# Micro-OLED_I2C.net
KiCad netlist of a schematic drawn in EAGLE
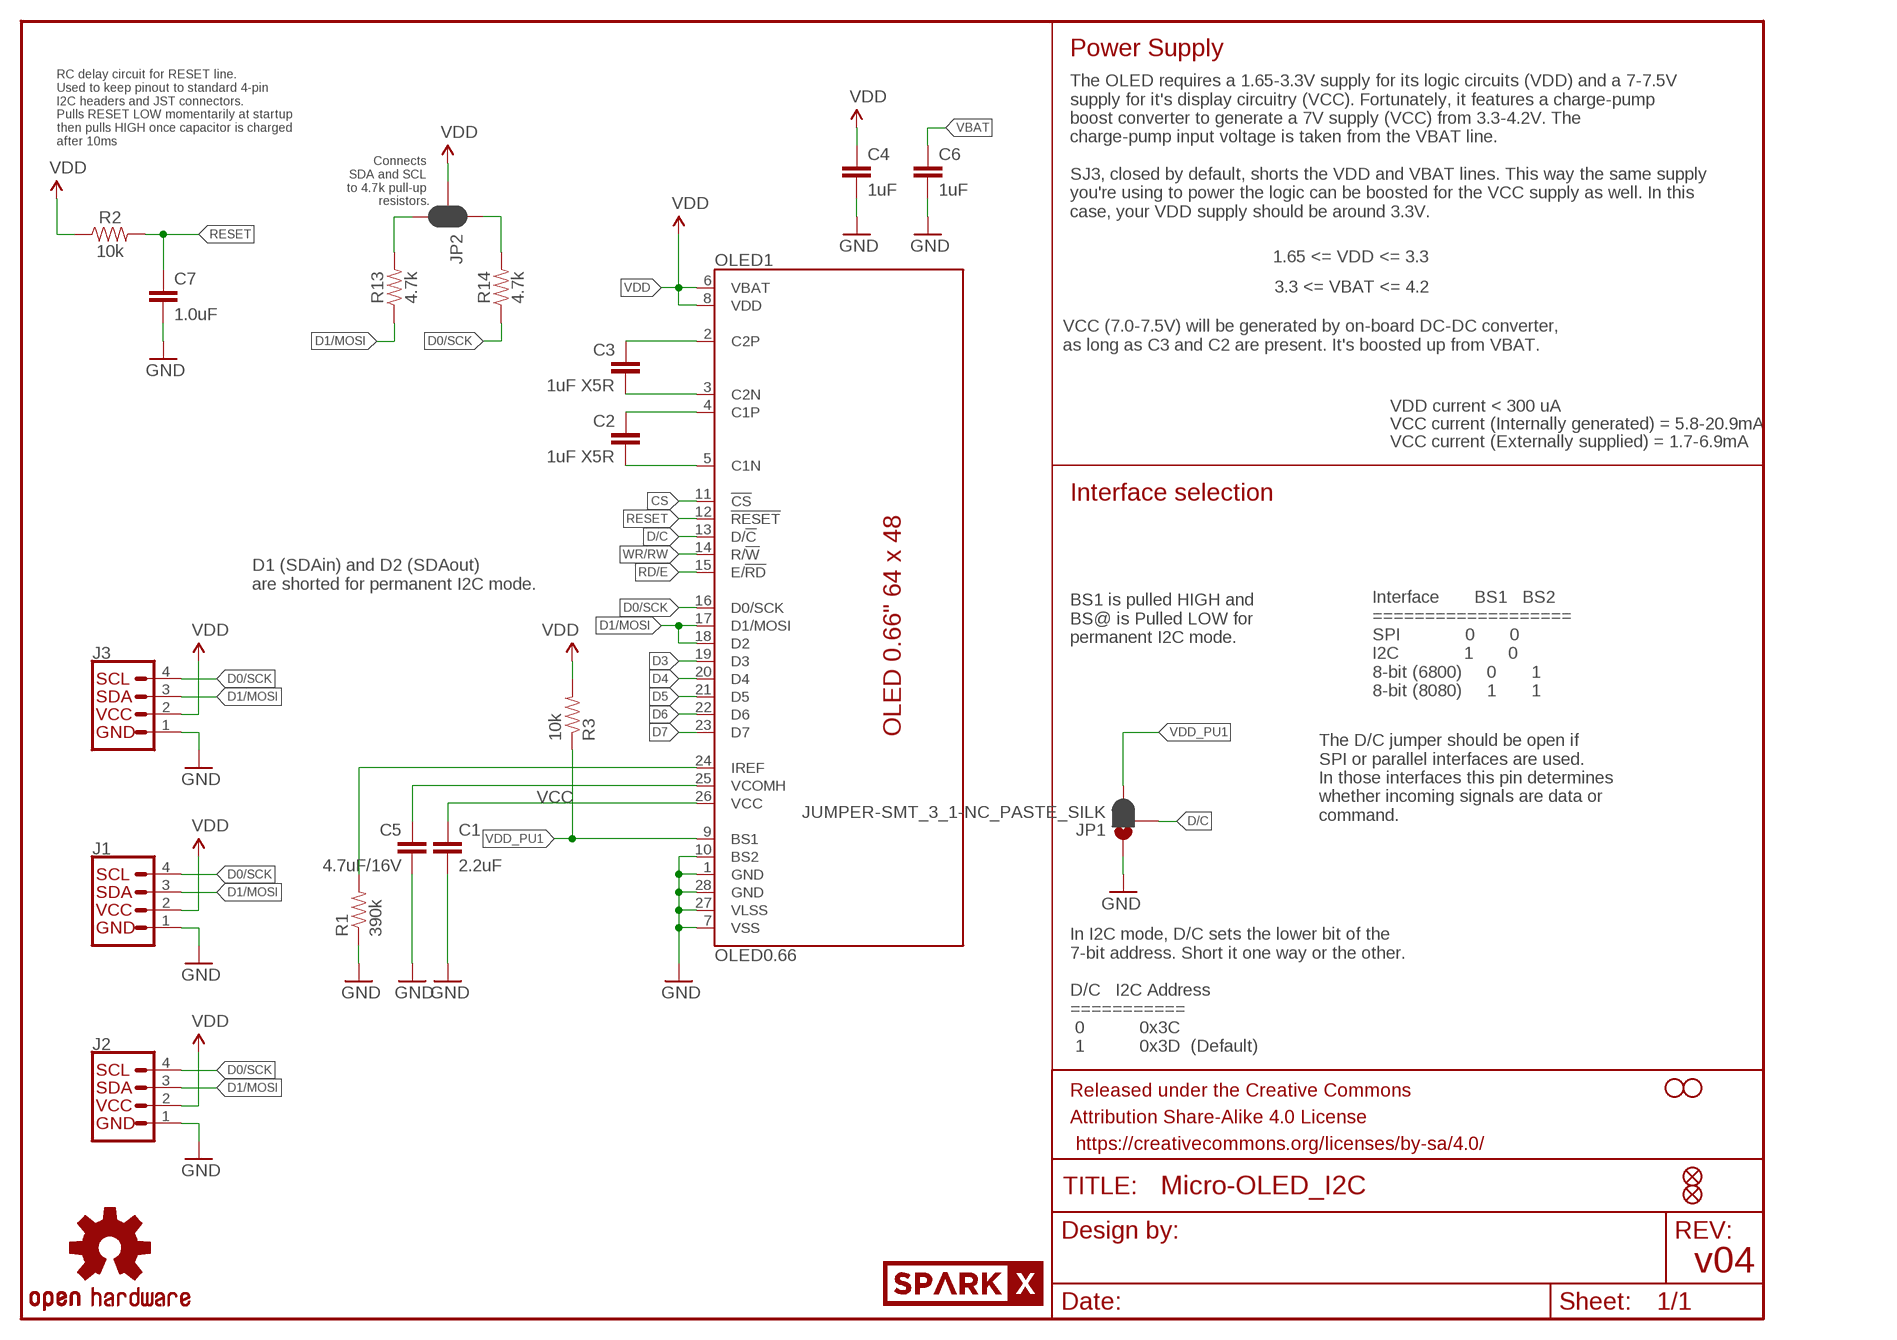
[diagram p0: schematic, sheet 1]

(export (version "E")
  (design (tool "Eeschema 10.0.6"))
  (components
    (comp (ref "C1")
      (value "2.2uF")
      (footprint "eagle-import:0805")
      (libsource (lib "eagle-import") (part "CAP0805"))
    )
    (comp (ref "C2")
      (value "1uF X5R")
      (footprint "eagle-import:0805")
      (libsource (lib "eagle-import") (part "CAP0805"))
    )
    (comp (ref "C3")
      (value "1uF X5R")
      (footprint "eagle-import:0805")
      (libsource (lib "eagle-import") (part "CAP0805"))
    )
    (comp (ref "C4")
      (value "1uF")
      (footprint "eagle-import:0603-CAP")
      (libsource (lib "eagle-import") (part "CAP0603-CAP"))
    )
    (comp (ref "C5")
      (value "4.7uF/16V")
      (footprint "eagle-import:1206")
      (libsource (lib "eagle-import") (part "CAP1206"))
    )
    (comp (ref "C6")
      (value "1uF")
      (footprint "eagle-import:0603-CAP")
      (libsource (lib "eagle-import") (part "CAP0603-CAP"))
    )
    (comp (ref "C7")
      (value "1.0uF")
      (footprint "eagle-import:0603")
      (libsource (lib "eagle-import") (part "1.0UF-0603-16V-10%"))
    )
    (comp (ref "FID1")
      (value "FIDUCIAL1X2")
      (footprint "eagle-import:FIDUCIAL-1X2")
      (libsource (lib "eagle-import") (part "FIDUCIAL1X2"))
    )
    (comp (ref "FID2")
      (value "FIDUCIAL1X2")
      (footprint "eagle-import:FIDUCIAL-1X2")
      (libsource (lib "eagle-import") (part "FIDUCIAL1X2"))
    )
    (comp (ref "FRAME1")
      (value "FRAME-LETTER")
      (footprint "eagle-import:CREATIVE_COMMONS")
      (libsource (lib "eagle-import") (part "FRAME-LETTER"))
    )
    (comp (ref "H1")
      (value "STAND-OFF")
      (footprint "eagle-import:STAND-OFF")
      (libsource (lib "eagle-import") (part "STAND-OFF"))
    )
    (comp (ref "H2")
      (value "STAND-OFF")
      (footprint "eagle-import:STAND-OFF")
      (libsource (lib "eagle-import") (part "STAND-OFF"))
    )
    (comp (ref "J1")
      (value "I2C_STANDARDJS-1MM")
      (footprint "eagle-import:1X04_1MM_RA")
      (libsource (lib "eagle-import") (part "I2C_STANDARDJS-1MM"))
    )
    (comp (ref "J2")
      (value "I2C_STANDARDJS-1MM")
      (footprint "eagle-import:1X04_1MM_RA")
      (libsource (lib "eagle-import") (part "I2C_STANDARDJS-1MM"))
    )
    (comp (ref "J3")
      (value "I2C_STANDARD_NO_SILK")
      (footprint "eagle-import:1X04_NO_SILK")
      (libsource (lib "eagle-import") (part "I2C_STANDARD_NO_SILK"))
    )
    (comp (ref "JP1")
      (value "JUMPER-SMT_3_1-NC_PASTE_SILK")
      (footprint "eagle-import:SMT-JUMPER_3_1-NC_PASTE_SILK")
      (libsource (lib "eagle-import") (part "JUMPER-SMT_3_1-NC_PASTE_SILK"))
    )
    (comp (ref "JP2")
      (value "JUMPER-SMT_3_2-NC_PASTE_SILK")
      (footprint "eagle-import:SMT-JUMPER_3_2-NC_PASTE_SILK")
      (libsource (lib "eagle-import") (part "JUMPER-SMT_3_2-NC_PASTE_SILK"))
    )
    (comp (ref "LOGO3")
      (value "OSHW-LOGOS")
      (footprint "eagle-import:OSHW-LOGO-S")
      (libsource (lib "eagle-import") (part "OSHW-LOGOS"))
    )
    (comp (ref "OLED1")
      (value "OLED0.66")
      (footprint "eagle-import:OLED-0.66-64X48")
      (libsource (lib "eagle-import") (part "OLED0.66"))
    )
    (comp (ref "R1")
      (value "390k")
      (footprint "eagle-import:0603-RES")
      (libsource (lib "eagle-import") (part "RESISTOR0603-RES"))
    )
    (comp (ref "R2")
      (value "10k")
      (footprint "eagle-import:0603")
      (libsource (lib "eagle-import") (part "10KOHM-0603-1/10W-1%"))
    )
    (comp (ref "R3")
      (value "10k")
      (footprint "eagle-import:0603-RES")
      (libsource (lib "eagle-import") (part "RESISTOR0603-RES"))
    )
    (comp (ref "R13")
      (value "4.7k")
      (footprint "eagle-import:0603")
      (libsource (lib "eagle-import") (part "4.7KOHM-0603-1/10W-1%"))
    )
    (comp (ref "R14")
      (value "4.7k")
      (footprint "eagle-import:0603")
      (libsource (lib "eagle-import") (part "4.7KOHM-0603-1/10W-1%"))
    )
    (comp (ref "U$1")
      (value "SPARKX-LOGO4")
      (footprint "eagle-import:SPARKX-MEDIUM")
      (libsource (lib "eagle-import") (part "SPARKX-LOGO4"))
    )
  )
  (nets
    (net (code "1") (name "/VCC") (class "Default")
      (node (ref "C1") (pin "1") (pinfunction "1_1") (pintype "passive"))
      (node (ref "OLED1") (pin "26") (pinfunction "VCC_26") (pintype "bidirectional"))
    )
    (net (code "2") (name "CS") (class "Default")
      (node (ref "OLED1") (pin "11") (pinfunction "~{CS}_11") (pintype "bidirectional"))
    )
    (net (code "3") (name "D0{slash}SCK") (class "Default")
      (node (ref "J1") (pin "4") (pinfunction "SCL_4") (pintype "passive"))
      (node (ref "J2") (pin "4") (pinfunction "SCL_4") (pintype "passive"))
      (node (ref "J3") (pin "4") (pinfunction "SCL_4") (pintype "passive"))
      (node (ref "OLED1") (pin "16") (pinfunction "D0/SCK_16") (pintype "bidirectional"))
      (node (ref "R14") (pin "1") (pinfunction "1_1") (pintype "passive"))
    )
    (net (code "4") (name "D1{slash}MOSI") (class "Default")
      (node (ref "J1") (pin "3") (pinfunction "SDA_3") (pintype "passive"))
      (node (ref "J2") (pin "3") (pinfunction "SDA_3") (pintype "passive"))
      (node (ref "J3") (pin "3") (pinfunction "SDA_3") (pintype "passive"))
      (node (ref "OLED1") (pin "17") (pinfunction "D1/MOSI_17") (pintype "bidirectional"))
      (node (ref "OLED1") (pin "18") (pinfunction "D2_18") (pintype "bidirectional"))
      (node (ref "R13") (pin "1") (pinfunction "1_1") (pintype "passive"))
    )
    (net (code "5") (name "D3") (class "Default")
      (node (ref "OLED1") (pin "19") (pinfunction "D3_19") (pintype "bidirectional"))
    )
    (net (code "6") (name "D4") (class "Default")
      (node (ref "OLED1") (pin "20") (pinfunction "D4_20") (pintype "bidirectional"))
    )
    (net (code "7") (name "D5") (class "Default")
      (node (ref "OLED1") (pin "21") (pinfunction "D5_21") (pintype "bidirectional"))
    )
    (net (code "8") (name "D6") (class "Default")
      (node (ref "OLED1") (pin "22") (pinfunction "D6_22") (pintype "bidirectional"))
    )
    (net (code "9") (name "D7") (class "Default")
      (node (ref "OLED1") (pin "23") (pinfunction "D7_23") (pintype "bidirectional"))
    )
    (net (code "10") (name "D{slash}C") (class "Default")
      (node (ref "JP1") (pin "2") (pinfunction "2_2") (pintype "passive"))
      (node (ref "OLED1") (pin "13") (pinfunction "D/~{C}_13") (pintype "bidirectional"))
    )
    (net (code "11") (name "GND") (class "Default")
      (node (ref "C1") (pin "2") (pinfunction "2_2") (pintype "passive"))
      (node (ref "C4") (pin "2") (pinfunction "2_2") (pintype "passive"))
      (node (ref "C5") (pin "2") (pinfunction "2_2") (pintype "passive"))
      (node (ref "C6") (pin "2") (pinfunction "2_2") (pintype "passive"))
      (node (ref "C7") (pin "2") (pinfunction "2_2") (pintype "passive"))
      (node (ref "J1") (pin "1") (pinfunction "GND_1") (pintype "power_in"))
      (node (ref "J2") (pin "1") (pinfunction "GND_1") (pintype "power_in"))
      (node (ref "J3") (pin "1") (pinfunction "GND_1") (pintype "power_in"))
      (node (ref "JP1") (pin "1") (pinfunction "1_1") (pintype "passive"))
      (node (ref "OLED1") (pin "1") (pinfunction "GND_1") (pintype "bidirectional"))
      (node (ref "OLED1") (pin "10") (pinfunction "BS2_10") (pintype "bidirectional"))
      (node (ref "OLED1") (pin "27") (pinfunction "VLSS_27") (pintype "bidirectional"))
      (node (ref "OLED1") (pin "28") (pinfunction "GND_28") (pintype "bidirectional"))
      (node (ref "OLED1") (pin "7") (pinfunction "VSS_7") (pintype "bidirectional"))
      (node (ref "R1") (pin "1") (pinfunction "1_1") (pintype "passive"))
    )
    (net (code "12") (name "Net-(JP2-Pad1)") (class "Default")
      (node (ref "JP2") (pin "1") (pinfunction "1_1") (pintype "passive"))
      (node (ref "R14") (pin "2") (pinfunction "2_2") (pintype "passive"))
    )
    (net (code "13") (name "Net-(JP2-Pad3)") (class "Default")
      (node (ref "JP2") (pin "3") (pinfunction "3_3") (pintype "passive"))
      (node (ref "R13") (pin "2") (pinfunction "2_2") (pintype "passive"))
    )
    (net (code "14") (name "Net-(OLED1-C1N)") (class "Default")
      (node (ref "C2") (pin "2") (pinfunction "2_2") (pintype "passive"))
      (node (ref "OLED1") (pin "5") (pinfunction "C1N_5") (pintype "bidirectional"))
    )
    (net (code "15") (name "Net-(OLED1-C1P)") (class "Default")
      (node (ref "C2") (pin "1") (pinfunction "1_1") (pintype "passive"))
      (node (ref "OLED1") (pin "4") (pinfunction "C1P_4") (pintype "bidirectional"))
    )
    (net (code "16") (name "Net-(OLED1-C2N)") (class "Default")
      (node (ref "C3") (pin "2") (pinfunction "2_2") (pintype "passive"))
      (node (ref "OLED1") (pin "3") (pinfunction "C2N_3") (pintype "bidirectional"))
    )
    (net (code "17") (name "Net-(OLED1-C2P)") (class "Default")
      (node (ref "C3") (pin "1") (pinfunction "1_1") (pintype "passive"))
      (node (ref "OLED1") (pin "2") (pinfunction "C2P_2") (pintype "bidirectional"))
    )
    (net (code "18") (name "Net-(OLED1-IREF)") (class "Default")
      (node (ref "OLED1") (pin "24") (pinfunction "IREF_24") (pintype "bidirectional"))
      (node (ref "R1") (pin "2") (pinfunction "2_2") (pintype "passive"))
    )
    (net (code "19") (name "Net-(OLED1-VCOMH)") (class "Default")
      (node (ref "C5") (pin "1") (pinfunction "1_1") (pintype "passive"))
      (node (ref "OLED1") (pin "25") (pinfunction "VCOMH_25") (pintype "bidirectional"))
    )
    (net (code "20") (name "RD{slash}E") (class "Default")
      (node (ref "OLED1") (pin "15") (pinfunction "E/~{RD}_15") (pintype "bidirectional"))
    )
    (net (code "21") (name "RESET") (class "Default")
      (node (ref "C7") (pin "1") (pinfunction "1_1") (pintype "passive"))
      (node (ref "OLED1") (pin "12") (pinfunction "~{RESET}_12") (pintype "bidirectional"))
      (node (ref "R2") (pin "2") (pinfunction "2_2") (pintype "passive"))
    )
    (net (code "22") (name "VBAT") (class "Default")
      (node (ref "C6") (pin "1") (pinfunction "1_1") (pintype "passive"))
    )
    (net (code "23") (name "VDD") (class "Default")
      (node (ref "C4") (pin "1") (pinfunction "1_1") (pintype "passive"))
      (node (ref "J1") (pin "2") (pinfunction "VCC_2") (pintype "power_in"))
      (node (ref "J2") (pin "2") (pinfunction "VCC_2") (pintype "power_in"))
      (node (ref "J3") (pin "2") (pinfunction "VCC_2") (pintype "power_in"))
      (node (ref "JP2") (pin "2") (pinfunction "2_2") (pintype "passive"))
      (node (ref "OLED1") (pin "6") (pinfunction "VBAT_6") (pintype "bidirectional"))
      (node (ref "OLED1") (pin "8") (pinfunction "VDD_8") (pintype "bidirectional"))
      (node (ref "R2") (pin "1") (pinfunction "1_1") (pintype "passive"))
      (node (ref "R3") (pin "2") (pinfunction "2_2") (pintype "passive"))
    )
    (net (code "24") (name "VDD_PU1") (class "Default")
      (node (ref "JP1") (pin "3") (pinfunction "3_3") (pintype "passive"))
      (node (ref "OLED1") (pin "9") (pinfunction "BS1_9") (pintype "bidirectional"))
      (node (ref "R3") (pin "1") (pinfunction "1_1") (pintype "passive"))
    )
    (net (code "25") (name "WR{slash}RW") (class "Default")
      (node (ref "OLED1") (pin "14") (pinfunction "R/~{W}_14") (pintype "bidirectional"))
    )
  )
)
